# led_breakout.net
KiCad netlist of a schematic drawn in EAGLE
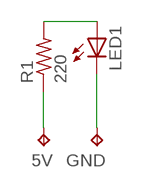
[diagram p0: schematic, sheet 1]

(export (version "E")
  (design (tool "Eeschema 10.0.6"))
  (components
    (comp (ref "5V")
      (value "TPTP13R")
      (footprint "eagle-import:TP13R")
      (libsource (lib "eagle-import") (part "TPTP13R"))
    )
    (comp (ref "GND")
      (value "TPTP13SQ")
      (footprint "eagle-import:TP13SQ")
      (libsource (lib "eagle-import") (part "TPTP13SQ"))
    )
    (comp (ref "LED1")
      (value "LEDSML0603")
      (footprint "eagle-import:SML0603")
      (libsource (lib "eagle-import") (part "LEDSML0603"))
    )
    (comp (ref "R1")
      (value "220")
      (footprint "eagle-import:R0603")
      (libsource (lib "eagle-import") (part "R-US_R0603"))
    )
  )
  (nets
    (net (code "1") (name "Net-(5V-PadTP)") (class "Default")
      (node (ref "5V") (pin "TP") (pinfunction "TP_TP") (pintype "input"))
      (node (ref "R1") (pin "1") (pinfunction "1_1") (pintype "passive"))
    )
    (net (code "2") (name "Net-(GND-PadTP)") (class "Default")
      (node (ref "GND") (pin "TP") (pinfunction "TP_TP") (pintype "input"))
      (node (ref "LED1") (pin "C") (pinfunction "C_C") (pintype "passive"))
    )
    (net (code "3") (name "Net-(LED1-PadA)") (class "Default")
      (node (ref "LED1") (pin "A") (pinfunction "A_A") (pintype "passive"))
      (node (ref "R1") (pin "2") (pinfunction "2_2") (pintype "passive"))
    )
  )
)
